# Controller.net
KiCad netlist of a schematic drawn in Altium Designer
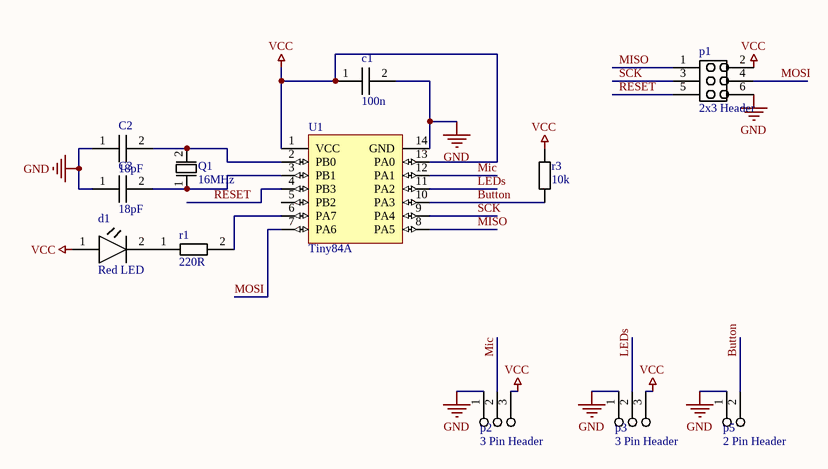
[diagram p0: µController.SchDoc]

(export (version "E")
  (design (tool "Eeschema 10.0.6"))
  (components
    (comp (ref "c1")
      (value "100n")
      (footprint "0805")
      (description "...F")
      (libsource (lib "Generic R-C") (part "0805 Capacitor"))
    )
    (comp (ref "C2")
      (value "18pF")
      (footprint "0603")
      (description "...F")
      (libsource (lib "Generic R-C") (part "0603 Capacitor"))
    )
    (comp (ref "C3")
      (value "18pF")
      (footprint "0603")
      (description "...F")
      (libsource (lib "Generic R-C") (part "0603 Capacitor"))
    )
    (comp (ref "d1")
      (value "Red LED")
      (footprint "0805 - diode")
      (description "Red diffused LED")
      (libsource (lib "Broadcom") (part "Red LED"))
    )
    (comp (ref "p1")
      (value "2x3 Header")
      (footprint "2x3-HeaderPin")
      (description "Header Pin")
      (libsource (lib "Multicomp") (part "2x3 Header"))
    )
    (comp (ref "p2")
      (value "3 Pin Header")
      (footprint "1x3-HeaderPin")
      (description "Header Pin")
      (libsource (lib "Multicomp") (part "3 Pin Header"))
    )
    (comp (ref "p3")
      (value "3 Pin Header")
      (footprint "1x3-HeaderPin")
      (description "Header Pin")
      (libsource (lib "Multicomp") (part "3 Pin Header"))
    )
    (comp (ref "p5")
      (value "2 Pin Header")
      (footprint "1x2-HeaderPin")
      (libsource (lib "Multicomp") (part "2 Pin Header"))
    )
    (comp (ref "Q1")
      (value "16MHz")
      (footprint "Crystal 488P")
      (description "...MHz")
      (libsource (lib "FOX Crystals") (part "Crystal"))
    )
    (comp (ref "r1")
      (value "220R")
      (footprint "0805")
      (description "...R")
      (libsource (lib "Generic R-C") (part "0805 Resistor"))
    )
    (comp (ref "r3")
      (value "10k")
      (footprint "0603")
      (description "...R")
      (libsource (lib "Generic R-C") (part "0603 Resistor"))
    )
    (comp (ref "U1")
      (value "Tiny84A")
      (footprint "SOIC14N")
      (description "ATTiny84A")
      (libsource (lib "Microchip-Atmel") (part "ATTiny84A"))
    )
  )
  (nets
    (net (code "1") (name "/Button") (class "Default")
      (node (ref "U1") (pin "10") (pinfunction "PA3_10") (pintype "bidirectional"))
      (node (ref "p5") (pin "2") (pinfunction "2_2") (pintype "passive"))
      (node (ref "r3") (pin "1") (pintype "passive"))
    )
    (net (code "2") (name "/LEDs") (class "Default")
      (node (ref "U1") (pin "11") (pinfunction "PA2_11") (pintype "bidirectional"))
      (node (ref "p3") (pin "2") (pinfunction "2_2") (pintype "passive"))
    )
    (net (code "3") (name "/MISO") (class "Default")
      (node (ref "U1") (pin "8") (pinfunction "PA5_8") (pintype "bidirectional"))
      (node (ref "p1") (pin "1") (pinfunction "1_1") (pintype "passive"))
    )
    (net (code "4") (name "/MOSI") (class "Default")
      (node (ref "U1") (pin "7") (pinfunction "PA6_7") (pintype "bidirectional"))
      (node (ref "p1") (pin "4") (pinfunction "4_4") (pintype "passive"))
    )
    (net (code "5") (name "/Mic") (class "Default")
      (node (ref "U1") (pin "12") (pinfunction "PA1_12") (pintype "bidirectional"))
      (node (ref "p2") (pin "2") (pinfunction "2_2") (pintype "passive"))
    )
    (net (code "6") (name "/RESET") (class "Default")
      (node (ref "U1") (pin "4") (pinfunction "PB3_4") (pintype "bidirectional"))
      (node (ref "p1") (pin "5") (pinfunction "5_5") (pintype "passive"))
    )
    (net (code "7") (name "/SCK") (class "Default")
      (node (ref "U1") (pin "9") (pinfunction "PA4_9") (pintype "bidirectional"))
      (node (ref "p1") (pin "3") (pinfunction "3_3") (pintype "passive"))
    )
    (net (code "8") (name "GND") (class "Default")
      (node (ref "C2") (pin "1") (pinfunction "1_1") (pintype "passive"))
      (node (ref "C3") (pin "1") (pinfunction "1_1") (pintype "passive"))
      (node (ref "U1") (pin "14") (pinfunction "GND_14") (pintype "power_in"))
      (node (ref "c1") (pin "2") (pintype "passive"))
      (node (ref "p1") (pin "6") (pinfunction "6_6") (pintype "passive"))
      (node (ref "p2") (pin "1") (pinfunction "1_1") (pintype "passive"))
      (node (ref "p3") (pin "1") (pinfunction "1_1") (pintype "passive"))
      (node (ref "p5") (pin "1") (pinfunction "1_1") (pintype "passive"))
    )
    (net (code "9") (name "Net-(U1-PA7)") (class "Default")
      (node (ref "U1") (pin "6") (pinfunction "PA7_6") (pintype "bidirectional"))
      (node (ref "r1") (pin "2") (pintype "passive"))
    )
    (net (code "10") (name "Net-(U1-PB0)") (class "Default")
      (node (ref "C2") (pin "2") (pinfunction "2_2") (pintype "passive"))
      (node (ref "Q1") (pin "2") (pinfunction "2_2") (pintype "passive"))
      (node (ref "U1") (pin "2") (pinfunction "PB0_2") (pintype "bidirectional"))
    )
    (net (code "11") (name "Net-(U1-PB1)") (class "Default")
      (node (ref "C3") (pin "2") (pinfunction "2_2") (pintype "passive"))
      (node (ref "Q1") (pin "1") (pinfunction "1_1") (pintype "passive"))
      (node (ref "U1") (pin "3") (pinfunction "PB1_3") (pintype "bidirectional"))
    )
    (net (code "12") (name "Net-(d1-Pad2)") (class "Default")
      (node (ref "d1") (pin "2") (pinfunction "2_2") (pintype "passive"))
      (node (ref "r1") (pin "1") (pintype "passive"))
    )
    (net (code "13") (name "VCC") (class "Default")
      (node (ref "U1") (pin "1") (pinfunction "VCC_1") (pintype "power_in"))
      (node (ref "U1") (pin "13") (pinfunction "PA0_13") (pintype "bidirectional"))
      (node (ref "c1") (pin "1") (pintype "passive"))
      (node (ref "d1") (pin "1") (pinfunction "1_1") (pintype "passive"))
      (node (ref "p1") (pin "2") (pinfunction "2_2") (pintype "passive"))
      (node (ref "p2") (pin "3") (pinfunction "3_3") (pintype "passive"))
      (node (ref "p3") (pin "3") (pinfunction "3_3") (pintype "passive"))
      (node (ref "r3") (pin "2") (pintype "passive"))
    )
    (net (code "14") (name "unconnected-(U1-PB2-Pad5)") (class "Default")
      (node (ref "U1") (pin "5") (pinfunction "PB2_5") (pintype "bidirectional"))
    )
  )
)
